# M133A.net
KiCad netlist of a schematic drawn in EAGLE
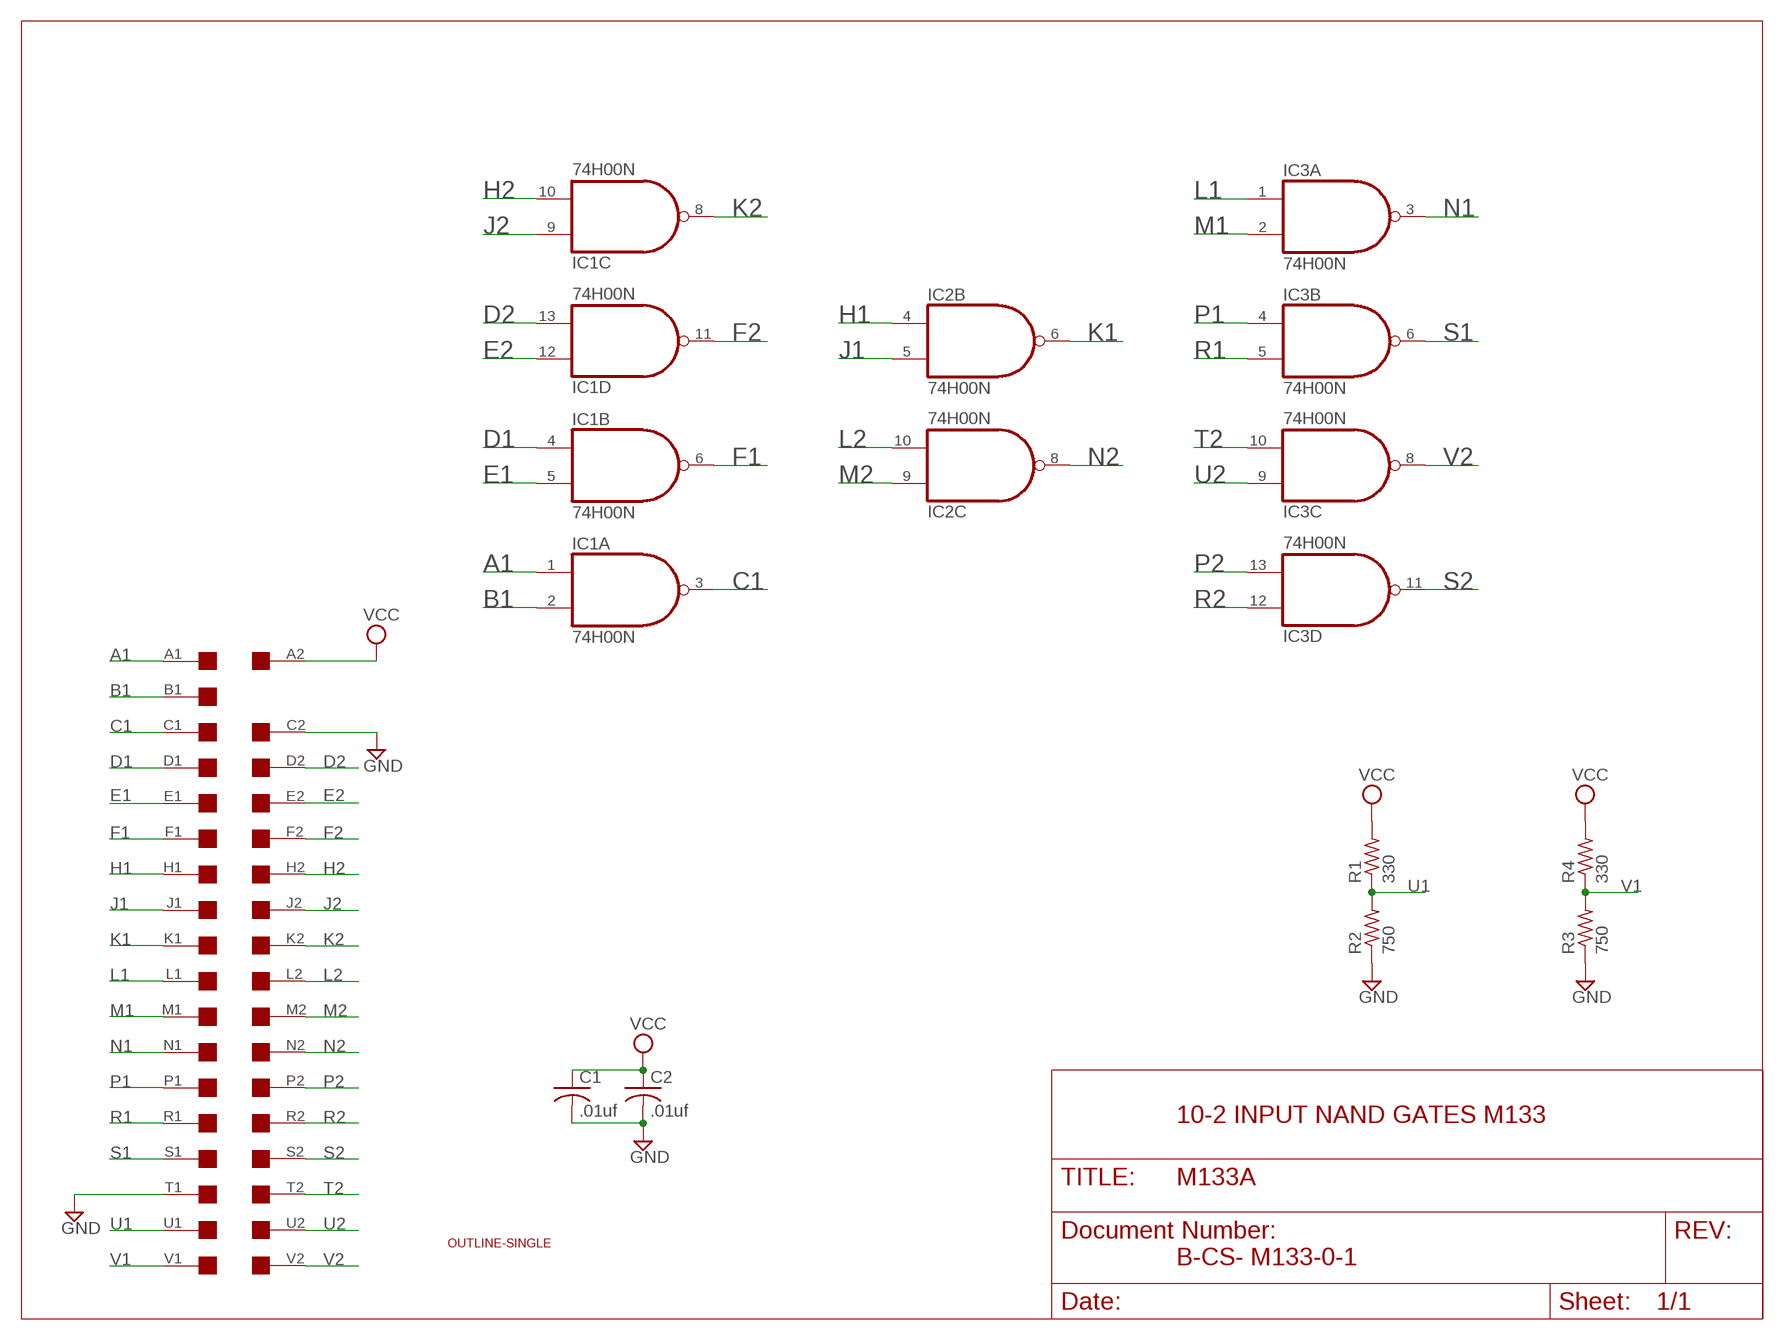
[diagram p0: schematic, sheet 1]

(export (version "E")
  (design (tool "Eeschema 10.0.6"))
  (components
    (comp (ref "C1")
      (value ".01uf")
      (footprint "eagle-import:C050-025X075")
      (libsource (lib "eagle-import") (part "C-US050-025X075"))
    )
    (comp (ref "C2")
      (value ".01uf")
      (footprint "eagle-import:C050-025X075")
      (libsource (lib "eagle-import") (part "C-US050-025X075"))
    )
    (comp (ref "IC1")
      (value "74H00N")
      (footprint "eagle-import:DIL14")
      (libsource (lib "eagle-import") (part "7400N"))
    )
    (comp (ref "IC2")
      (value "74H00N")
      (footprint "eagle-import:DIL14")
      (libsource (lib "eagle-import") (part "7400N"))
    )
    (comp (ref "IC3")
      (value "74H00N")
      (footprint "eagle-import:DIL14")
      (libsource (lib "eagle-import") (part "7400N"))
    )
    (comp (ref "R1")
      (value "330")
      (footprint "eagle-import:0207_10")
      (libsource (lib "eagle-import") (part "R-US_0207/10"))
    )
    (comp (ref "R2")
      (value "750")
      (footprint "eagle-import:0207_10")
      (libsource (lib "eagle-import") (part "R-US_0207/10"))
    )
    (comp (ref "R3")
      (value "750")
      (footprint "eagle-import:0207_10")
      (libsource (lib "eagle-import") (part "R-US_0207/10"))
    )
    (comp (ref "R4")
      (value "330")
      (footprint "eagle-import:0207_10")
      (libsource (lib "eagle-import") (part "R-US_0207/10"))
    )
    (comp (ref "U$1")
      (value "OUTLINE-SINGLE")
      (footprint "eagle-import:SINGLE")
      (libsource (lib "eagle-import") (part "OUTLINE-SINGLE"))
    )
    (comp (ref "U$4")
      (value "SINGLE")
      (footprint "eagle-import:EDGE-CON2")
      (libsource (lib "eagle-import") (part "SINGLE"))
    )
  )
  (nets
    (net (code "1") (name "/A1") (class "Default")
      (node (ref "IC1") (pin "1") (pinfunction "I0_1") (pintype "input"))
      (node (ref "U$4") (pin "A1") (pinfunction "1_A1") (pintype "bidirectional"))
    )
    (net (code "2") (name "/B1") (class "Default")
      (node (ref "IC1") (pin "2") (pinfunction "I1_2") (pintype "input"))
      (node (ref "U$4") (pin "B1") (pinfunction "1_B1") (pintype "bidirectional"))
    )
    (net (code "3") (name "/C1") (class "Default")
      (node (ref "IC1") (pin "3") (pinfunction "O_3") (pintype "output"))
      (node (ref "U$4") (pin "C1") (pinfunction "1_C1") (pintype "bidirectional"))
    )
    (net (code "4") (name "/D1") (class "Default")
      (node (ref "IC1") (pin "4") (pinfunction "I0_4") (pintype "input"))
      (node (ref "U$4") (pin "D1") (pinfunction "1_D1") (pintype "bidirectional"))
    )
    (net (code "5") (name "/D2") (class "Default")
      (node (ref "IC1") (pin "13") (pinfunction "I1_13") (pintype "input"))
      (node (ref "U$4") (pin "D2") (pinfunction "1_D2") (pintype "bidirectional"))
    )
    (net (code "6") (name "/E1") (class "Default")
      (node (ref "IC1") (pin "5") (pinfunction "I1_5") (pintype "input"))
      (node (ref "U$4") (pin "E1") (pinfunction "1_E1") (pintype "bidirectional"))
    )
    (net (code "7") (name "/E2") (class "Default")
      (node (ref "IC1") (pin "12") (pinfunction "I0_12") (pintype "input"))
      (node (ref "U$4") (pin "E2") (pinfunction "1_E2") (pintype "bidirectional"))
    )
    (net (code "8") (name "/F1") (class "Default")
      (node (ref "IC1") (pin "6") (pinfunction "O_6") (pintype "output"))
      (node (ref "U$4") (pin "F1") (pinfunction "1_F1") (pintype "bidirectional"))
    )
    (net (code "9") (name "/F2") (class "Default")
      (node (ref "IC1") (pin "11") (pinfunction "O_11") (pintype "output"))
      (node (ref "U$4") (pin "F2") (pinfunction "1_F2") (pintype "bidirectional"))
    )
    (net (code "10") (name "/H1") (class "Default")
      (node (ref "IC2") (pin "4") (pinfunction "I0_4") (pintype "input"))
      (node (ref "U$4") (pin "H1") (pinfunction "1_H1") (pintype "bidirectional"))
    )
    (net (code "11") (name "/H2") (class "Default")
      (node (ref "IC1") (pin "10") (pinfunction "I1_10") (pintype "input"))
      (node (ref "U$4") (pin "H2") (pinfunction "1_H2") (pintype "bidirectional"))
    )
    (net (code "12") (name "/J1") (class "Default")
      (node (ref "IC2") (pin "5") (pinfunction "I1_5") (pintype "input"))
      (node (ref "U$4") (pin "J1") (pinfunction "1_J1") (pintype "bidirectional"))
    )
    (net (code "13") (name "/J2") (class "Default")
      (node (ref "IC1") (pin "9") (pinfunction "I0_9") (pintype "input"))
      (node (ref "U$4") (pin "J2") (pinfunction "1_J2") (pintype "bidirectional"))
    )
    (net (code "14") (name "/K1") (class "Default")
      (node (ref "IC2") (pin "6") (pinfunction "O_6") (pintype "output"))
      (node (ref "U$4") (pin "K1") (pinfunction "1_K1") (pintype "bidirectional"))
    )
    (net (code "15") (name "/K2") (class "Default")
      (node (ref "IC1") (pin "8") (pinfunction "O_8") (pintype "output"))
      (node (ref "U$4") (pin "K2") (pinfunction "1_K2") (pintype "bidirectional"))
    )
    (net (code "16") (name "/L1") (class "Default")
      (node (ref "IC3") (pin "1") (pinfunction "I0_1") (pintype "input"))
      (node (ref "U$4") (pin "L1") (pinfunction "1_L1") (pintype "bidirectional"))
    )
    (net (code "17") (name "/L2") (class "Default")
      (node (ref "IC2") (pin "10") (pinfunction "I1_10") (pintype "input"))
      (node (ref "U$4") (pin "L2") (pinfunction "1_L2") (pintype "bidirectional"))
    )
    (net (code "18") (name "/M1") (class "Default")
      (node (ref "IC3") (pin "2") (pinfunction "I1_2") (pintype "input"))
      (node (ref "U$4") (pin "M1") (pinfunction "1_M1") (pintype "bidirectional"))
    )
    (net (code "19") (name "/M2") (class "Default")
      (node (ref "IC2") (pin "9") (pinfunction "I0_9") (pintype "input"))
      (node (ref "U$4") (pin "M2") (pinfunction "1_M2") (pintype "bidirectional"))
    )
    (net (code "20") (name "/N1") (class "Default")
      (node (ref "IC3") (pin "3") (pinfunction "O_3") (pintype "output"))
      (node (ref "U$4") (pin "N1") (pinfunction "1_N1") (pintype "bidirectional"))
    )
    (net (code "21") (name "/N2") (class "Default")
      (node (ref "IC2") (pin "8") (pinfunction "O_8") (pintype "output"))
      (node (ref "U$4") (pin "N2") (pinfunction "1_N2") (pintype "bidirectional"))
    )
    (net (code "22") (name "/P1") (class "Default")
      (node (ref "IC3") (pin "4") (pinfunction "I0_4") (pintype "input"))
      (node (ref "U$4") (pin "P1") (pinfunction "1_P1") (pintype "bidirectional"))
    )
    (net (code "23") (name "/P2") (class "Default")
      (node (ref "IC3") (pin "13") (pinfunction "I1_13") (pintype "input"))
      (node (ref "U$4") (pin "P2") (pinfunction "1_P2") (pintype "bidirectional"))
    )
    (net (code "24") (name "/R1") (class "Default")
      (node (ref "IC3") (pin "5") (pinfunction "I1_5") (pintype "input"))
      (node (ref "U$4") (pin "R1") (pinfunction "1_R1") (pintype "bidirectional"))
    )
    (net (code "25") (name "/R2") (class "Default")
      (node (ref "IC3") (pin "12") (pinfunction "I0_12") (pintype "input"))
      (node (ref "U$4") (pin "R2") (pinfunction "1_R2") (pintype "bidirectional"))
    )
    (net (code "26") (name "/S1") (class "Default")
      (node (ref "IC3") (pin "6") (pinfunction "O_6") (pintype "output"))
      (node (ref "U$4") (pin "S1") (pinfunction "1_S1") (pintype "bidirectional"))
    )
    (net (code "27") (name "/S2") (class "Default")
      (node (ref "IC3") (pin "11") (pinfunction "O_11") (pintype "output"))
      (node (ref "U$4") (pin "S2") (pinfunction "1_S2") (pintype "bidirectional"))
    )
    (net (code "28") (name "/T2") (class "Default")
      (node (ref "IC3") (pin "10") (pinfunction "I1_10") (pintype "input"))
      (node (ref "U$4") (pin "T2") (pinfunction "1_T2") (pintype "bidirectional"))
    )
    (net (code "29") (name "/U1") (class "Default")
      (node (ref "R1") (pin "1") (pinfunction "1_1") (pintype "passive"))
      (node (ref "R2") (pin "2") (pinfunction "2_2") (pintype "passive"))
      (node (ref "U$4") (pin "U1") (pinfunction "1_U1") (pintype "bidirectional"))
    )
    (net (code "30") (name "/U2") (class "Default")
      (node (ref "IC3") (pin "9") (pinfunction "I0_9") (pintype "input"))
      (node (ref "U$4") (pin "U2") (pinfunction "1_U2") (pintype "bidirectional"))
    )
    (net (code "31") (name "/V1") (class "Default")
      (node (ref "R3") (pin "2") (pinfunction "2_2") (pintype "passive"))
      (node (ref "R4") (pin "1") (pinfunction "1_1") (pintype "passive"))
      (node (ref "U$4") (pin "V1") (pinfunction "1_V1") (pintype "bidirectional"))
    )
    (net (code "32") (name "/V2") (class "Default")
      (node (ref "IC3") (pin "8") (pinfunction "O_8") (pintype "output"))
      (node (ref "U$4") (pin "V2") (pinfunction "1_V2") (pintype "bidirectional"))
    )
    (net (code "33") (name "GND") (class "Default")
      (node (ref "C1") (pin "2") (pinfunction "2_2") (pintype "passive"))
      (node (ref "C2") (pin "2") (pinfunction "2_2") (pintype "passive"))
      (node (ref "R2") (pin "1") (pinfunction "1_1") (pintype "passive"))
      (node (ref "R3") (pin "1") (pinfunction "1_1") (pintype "passive"))
      (node (ref "U$4") (pin "C2") (pinfunction "1_C2") (pintype "bidirectional"))
      (node (ref "U$4") (pin "T1") (pinfunction "1_T1") (pintype "bidirectional"))
    )
    (net (code "34") (name "VCC") (class "Default")
      (node (ref "C1") (pin "1") (pinfunction "1_1") (pintype "passive"))
      (node (ref "C2") (pin "1") (pinfunction "1_1") (pintype "passive"))
      (node (ref "R1") (pin "2") (pinfunction "2_2") (pintype "passive"))
      (node (ref "R4") (pin "2") (pinfunction "2_2") (pintype "passive"))
      (node (ref "U$4") (pin "A2") (pinfunction "1_A2") (pintype "bidirectional"))
    )
  )
)
